# Sheet1.net
KiCad netlist of a schematic drawn in Altium Designer
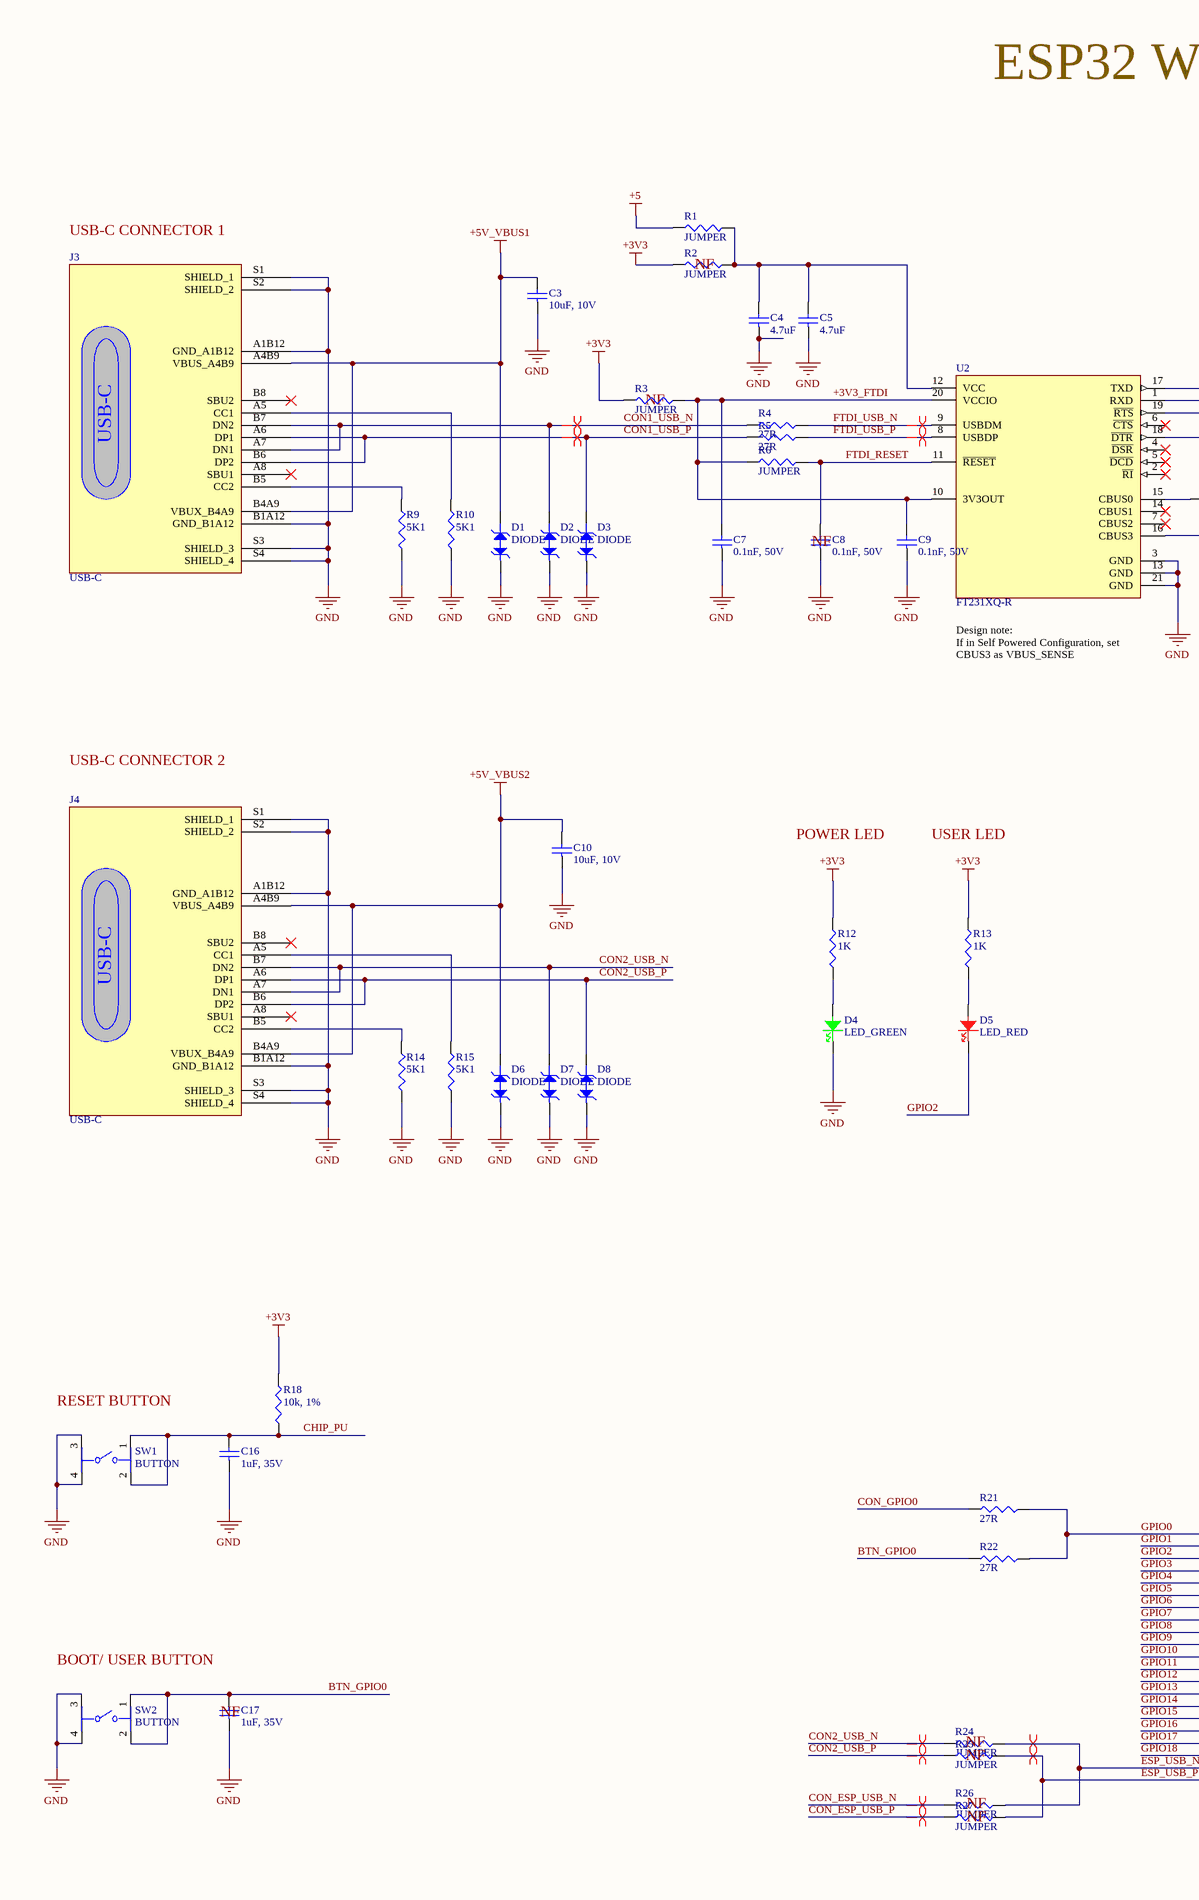
[diagram p0: Sheet1.SchDoc, left]
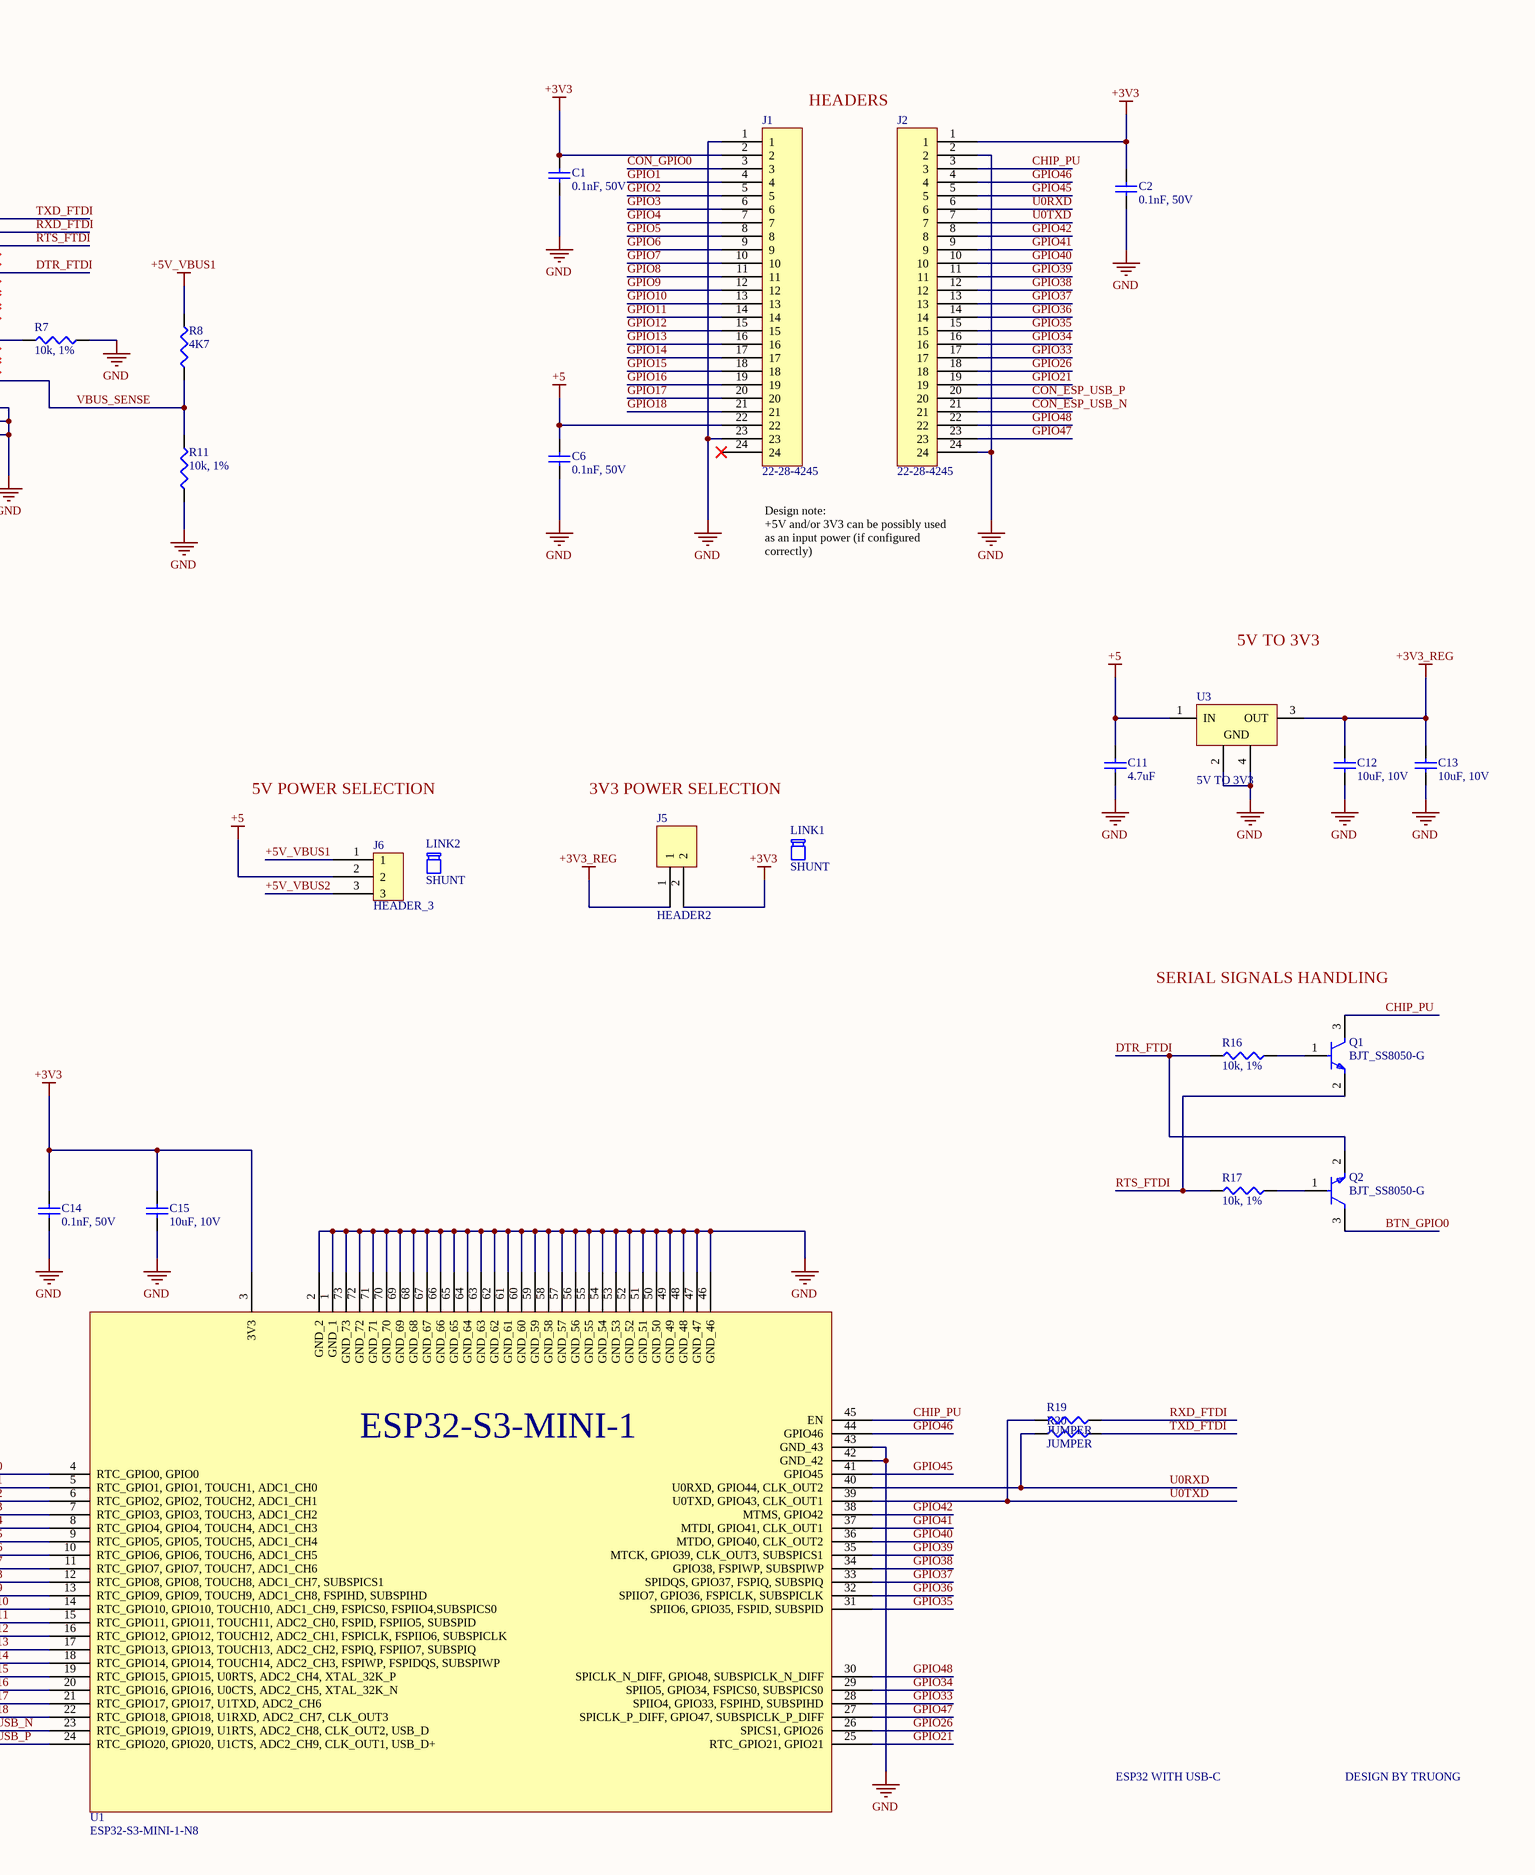
[diagram p1: Sheet1.SchDoc, right]

(export (version "E")
  (design (tool "Eeschema 10.0.6"))
  (components
    (comp (ref "C1")
      (value "0.1nF, 50V")
      (footprint "CAPC1005X70N")
      (description "CAP CER 0.1UF 50V X7R 0402")
      (fields
        (field (name "MANUFACTURER") "Samsung Electro-Mechanics")
        (field (name "MANUFACTURER PART NUMBER") "CL05B104KB5NNWC")
      )
      (libsource (lib "ESP32_CUSTOM_SCH.PrjPcb") (part "CL05B104KB5NNWC"))
    )
    (comp (ref "C2")
      (value "0.1nF, 50V")
      (footprint "CAPC1005X70N")
      (description "CAP CER 0.1UF 50V X7R 0402")
      (fields
        (field (name "MANUFACTURER") "Samsung Electro-Mechanics")
        (field (name "MANUFACTURER PART NUMBER") "CL05B104KB5NNWC")
      )
      (libsource (lib "ESP32_CUSTOM_SCH.PrjPcb") (part "CL05B104KB5NNWC"))
    )
    (comp (ref "C3")
      (value "10uF, 10V")
      (footprint "CAPC1005X70N")
      (description "CAP CER 10UF 10V X5R 0402")
      (fields
        (field (name "MANUFACTURER") "Samsung Electro-Mechanics")
        (field (name "MANUFACTURER PART NUMBER") "CL05A106MP5NUNC")
      )
      (libsource (lib "ESP32_CUSTOM_SCH.PrjPcb") (part "CL05A106MP5NUNC"))
    )
    (comp (ref "C4")
      (value "4.7uF")
      (footprint "CAPC1005X70N")
      (description "CAP CER 4.7UF 16V X5R 0402")
      (fields
        (field (name "MANUFACTURER") "Samsung Electro-Mechanics")
        (field (name "MANUFACTURER PART NUMBER") "CL05A475MO5NUNC")
      )
      (libsource (lib "ESP32_CUSTOM_SCH.PrjPcb") (part "CL05A475MO5NUNC"))
    )
    (comp (ref "C5")
      (value "4.7uF")
      (footprint "CAPC1005X70N")
      (description "CAP CER 4.7UF 16V X5R 0402")
      (fields
        (field (name "MANUFACTURER") "Samsung Electro-Mechanics")
        (field (name "MANUFACTURER PART NUMBER") "CL05A475MO5NUNC")
      )
      (libsource (lib "ESP32_CUSTOM_SCH.PrjPcb") (part "CL05A475MO5NUNC"))
    )
    (comp (ref "C6")
      (value "0.1nF, 50V")
      (footprint "CAPC1005X70N")
      (description "CAP CER 0.1UF 50V X7R 0402")
      (fields
        (field (name "MANUFACTURER") "Samsung Electro-Mechanics")
        (field (name "MANUFACTURER PART NUMBER") "CL05B104KB5NNWC")
      )
      (libsource (lib "ESP32_CUSTOM_SCH.PrjPcb") (part "CL05B104KB5NNWC"))
    )
    (comp (ref "C7")
      (value "0.1nF, 50V")
      (footprint "CAPC1005X70N")
      (description "CAP CER 0.1UF 50V X7R 0402")
      (fields
        (field (name "MANUFACTURER") "Samsung Electro-Mechanics")
        (field (name "MANUFACTURER PART NUMBER") "CL05B104KB5NNWC")
      )
      (libsource (lib "ESP32_CUSTOM_SCH.PrjPcb") (part "CL05B104KB5NNWC"))
    )
    (comp (ref "C8")
      (value "0.1nF, 50V")
      (footprint "CAPC1005X70N")
      (description "CAP CER 0.1UF 50V X7R 0402")
      (fields
        (field (name "MANUFACTURER") "Samsung Electro-Mechanics")
        (field (name "MANUFACTURER PART NUMBER") "CL05B104KB5NNWC")
      )
      (libsource (lib "ESP32_CUSTOM_SCH.PrjPcb") (part "CL05B104KB5NNWC"))
    )
    (comp (ref "C9")
      (value "0.1nF, 50V")
      (footprint "CAPC1005X70N")
      (description "CAP CER 0.1UF 50V X7R 0402")
      (fields
        (field (name "MANUFACTURER") "Samsung Electro-Mechanics")
        (field (name "MANUFACTURER PART NUMBER") "CL05B104KB5NNWC")
      )
      (libsource (lib "ESP32_CUSTOM_SCH.PrjPcb") (part "CL05B104KB5NNWC"))
    )
    (comp (ref "C10")
      (value "10uF, 10V")
      (footprint "CAPC1005X70N")
      (description "CAP CER 10UF 10V X5R 0402")
      (fields
        (field (name "MANUFACTURER") "Samsung Electro-Mechanics")
        (field (name "MANUFACTURER PART NUMBER") "CL05A106MP5NUNC")
      )
      (libsource (lib "ESP32_CUSTOM_SCH.PrjPcb") (part "CL05A106MP5NUNC"))
    )
    (comp (ref "C11")
      (value "4.7uF")
      (footprint "CAPC1005X70N")
      (description "CAP CER 4.7UF 16V X5R 0402")
      (fields
        (field (name "MANUFACTURER") "Samsung Electro-Mechanics")
        (field (name "MANUFACTURER PART NUMBER") "CL05A475MO5NUNC")
      )
      (libsource (lib "ESP32_CUSTOM_SCH.PrjPcb") (part "CL05A475MO5NUNC"))
    )
    (comp (ref "C12")
      (value "10uF, 10V")
      (footprint "CAPC1005X70N")
      (description "CAP CER 10UF 10V X5R 0402")
      (fields
        (field (name "MANUFACTURER") "Samsung Electro-Mechanics")
        (field (name "MANUFACTURER PART NUMBER") "CL05A106MP5NUNC")
      )
      (libsource (lib "ESP32_CUSTOM_SCH.PrjPcb") (part "CL05A106MP5NUNC"))
    )
    (comp (ref "C13")
      (value "10uF, 10V")
      (footprint "CAPC1005X70N")
      (description "CAP CER 10UF 10V X5R 0402")
      (fields
        (field (name "MANUFACTURER") "Samsung Electro-Mechanics")
        (field (name "MANUFACTURER PART NUMBER") "CL05A106MP5NUNC")
      )
      (libsource (lib "ESP32_CUSTOM_SCH.PrjPcb") (part "CL05A106MP5NUNC"))
    )
    (comp (ref "C14")
      (value "0.1nF, 50V")
      (footprint "CAPC1005X70N")
      (description "CAP CER 0.1UF 50V X7R 0402")
      (fields
        (field (name "MANUFACTURER") "Samsung Electro-Mechanics")
        (field (name "MANUFACTURER PART NUMBER") "CL05B104KB5NNWC")
      )
      (libsource (lib "ESP32_CUSTOM_SCH.PrjPcb") (part "CL05B104KB5NNWC"))
    )
    (comp (ref "C15")
      (value "10uF, 10V")
      (footprint "CAPC1005X70N")
      (description "CAP CER 10UF 10V X5R 0402")
      (fields
        (field (name "MANUFACTURER") "Samsung Electro-Mechanics")
        (field (name "MANUFACTURER PART NUMBER") "CL05A106MP5NUNC")
      )
      (libsource (lib "ESP32_CUSTOM_SCH.PrjPcb") (part "CL05A106MP5NUNC"))
    )
    (comp (ref "C16")
      (value "1uF, 35V")
      (footprint "CAPC1005X70N")
      (description "CAP CER 1UF 35V X5R 0402")
      (fields
        (field (name "MANUFACTURER") "Murata")
        (field (name "MANUFACTURER PART NUMBER") "GRM155R6YA105KE11D")
      )
      (libsource (lib "ESP32_CUSTOM_SCH.PrjPcb") (part "GRM155R6YA105KE11D"))
    )
    (comp (ref "C17")
      (value "1uF, 35V")
      (footprint "CAPC1005X70N")
      (description "CAP CER 1UF 35V X5R 0402")
      (fields
        (field (name "MANUFACTURER") "Murata")
        (field (name "MANUFACTURER PART NUMBER") "GRM155R6YA105KE11D")
      )
      (libsource (lib "ESP32_CUSTOM_SCH.PrjPcb") (part "GRM155R6YA105KE11D"))
    )
    (comp (ref "D1")
      (value "DIODE")
      (footprint "SOD882")
      (description "TVS DIODE 5.3VWM 12VC SOD882")
      (fields
        (field (name "MANUFACTURER") "Littelfuse")
        (field (name "MANUFACTURER PART NUMBER") "AQ3045-01ETG")
      )
      (libsource (lib "ESP32_CUSTOM_SCH.PrjPcb") (part "AQ3045-01ETG"))
    )
    (comp (ref "D2")
      (value "DIODE")
      (footprint "SOD882")
      (description "TVS DIODE 5.3VWM 12VC SOD882")
      (fields
        (field (name "MANUFACTURER") "Littelfuse")
        (field (name "MANUFACTURER PART NUMBER") "AQ3045-01ETG")
      )
      (libsource (lib "ESP32_CUSTOM_SCH.PrjPcb") (part "AQ3045-01ETG"))
    )
    (comp (ref "D3")
      (value "DIODE")
      (footprint "SOD882")
      (description "TVS DIODE 5.3VWM 12VC SOD882")
      (fields
        (field (name "MANUFACTURER") "Littelfuse")
        (field (name "MANUFACTURER PART NUMBER") "AQ3045-01ETG")
      )
      (libsource (lib "ESP32_CUSTOM_SCH.PrjPcb") (part "AQ3045-01ETG"))
    )
    (comp (ref "D4")
      (value "LED_GREEN")
      (footprint "LED0402_GREEN")
      (description "LED GREEN 0402 SMD")
      (fields
        (field (name "MANUFACTURER") "Vishay")
        (field (name "MANUFACTURER PART NUMBER") "VLMTG1500-GS08")
      )
      (libsource (lib "ESP32_CUSTOM_SCH.PrjPcb") (part "VLMTG1500-GS08"))
    )
    (comp (ref "D5")
      (value "LED_RED")
      (footprint "LED0402_RED")
      (description "LED RED 0402 SMD")
      (fields
        (field (name "MANUFACTURER") "Vishay")
        (field (name "MANUFACTURER PART NUMBER") "VLMS1500-GS08")
      )
      (libsource (lib "ESP32_CUSTOM_SCH.PrjPcb") (part "VLMS1500-GS08"))
    )
    (comp (ref "D6")
      (value "DIODE")
      (footprint "SOD882")
      (description "TVS DIODE 5.3VWM 12VC SOD882")
      (fields
        (field (name "MANUFACTURER") "Littelfuse")
        (field (name "MANUFACTURER PART NUMBER") "AQ3045-01ETG")
      )
      (libsource (lib "ESP32_CUSTOM_SCH.PrjPcb") (part "AQ3045-01ETG"))
    )
    (comp (ref "D7")
      (value "DIODE")
      (footprint "SOD882")
      (description "TVS DIODE 5.3VWM 12VC SOD882")
      (fields
        (field (name "MANUFACTURER") "Littelfuse")
        (field (name "MANUFACTURER PART NUMBER") "AQ3045-01ETG")
      )
      (libsource (lib "ESP32_CUSTOM_SCH.PrjPcb") (part "AQ3045-01ETG"))
    )
    (comp (ref "D8")
      (value "DIODE")
      (footprint "SOD882")
      (description "TVS DIODE 5.3VWM 12VC SOD882")
      (fields
        (field (name "MANUFACTURER") "Littelfuse")
        (field (name "MANUFACTURER PART NUMBER") "AQ3045-01ETG")
      )
      (libsource (lib "ESP32_CUSTOM_SCH.PrjPcb") (part "AQ3045-01ETG"))
    )
    (comp (ref "J1")
      (value "22-28-4245")
      (footprint "HDR_1X24_2.55MM")
      (description "CONN HEADER VERT 24POS 2.54MM")
      (fields (field (name "MANUFACTURER") "Molex") (field (name "LCSC PART NUMBER") "C7145888"))
      (libsource (lib "") (part "22-28-4245_1"))
    )
    (comp (ref "J2")
      (value "22-28-4245")
      (footprint "HDR_1X24_2.55MM")
      (description "CONN HEADER VERT 24POS 2.54MM")
      (fields (field (name "MANUFACTURER") "Molex") (field (name "LCSC PART NUMBER") "C7145888"))
      (libsource (lib "ESP32_CUSTOM_SCH.PrjPcb") (part "22-28-4245"))
    )
    (comp (ref "J3")
      (value "USB-C")
      (footprint "FP-2171790001-MFG")
      (description "CONN RCP USB2.0 TYP C 24P SMD RA")
      (fields (field (name "MANUFACTURER") "Molex") (field (name "MANUFACTURER PART NUMBER") "217179-0001"))
      (libsource (lib "ESP32_CUSTOM_SCH.PrjPcb") (part "217179-0001"))
    )
    (comp (ref "J4")
      (value "USB-C")
      (footprint "FP-2171790001-MFG")
      (description "CONN RCP USB2.0 TYP C 24P SMD RA")
      (fields (field (name "MANUFACTURER") "Molex") (field (name "MANUFACTURER PART NUMBER") "217179-0001"))
      (libsource (lib "ESP32_CUSTOM_SCH.PrjPcb") (part "217179-0001"))
    )
    (comp (ref "J5")
      (value "HEADER2")
      (footprint "HDR_1X2_1.27MM")
      (description "CONN HEADER VERT 2POS 1.27MM")
      (fields
        (field (name "MANUFACTURER") "Samtec")
        (field (name "MANUFACTURER PART NUMBER") "FTS-102-01-L-S")
      )
      (libsource (lib "ESP32_CUSTOM_SCH.PrjPcb") (part "FTS-102-01-L-S"))
    )
    (comp (ref "J6")
      (value "HEADER_3")
      (footprint "HDR_1X3_1.27MM")
      (description "CONN HEADER VERT 3POS 1.27MM")
      (fields
        (field (name "MANUFACTURER") "Samtec")
        (field (name "MANUFACTURER PART NUMBER") "FTS-103-01-F-S")
      )
      (libsource (lib "ESP32_CUSTOM_SCH.PrjPcb") (part "FTS-103-01-F-S"))
    )
    (comp (ref "LINK1")
      (value "SHUNT")
      (description "CONN SHUNT 1.27MM RED")
      (fields (field (name "MANUFACTURER") "Harwin") (field (name "MANUFACTURER PART NUMBER") "M50-1920005"))
      (libsource (lib "ESP32_CUSTOM_SCH.PrjPcb") (part "M50-1920005"))
    )
    (comp (ref "LINK2")
      (value "SHUNT")
      (description "CONN SHUNT 1.27MM RED")
      (fields (field (name "MANUFACTURER") "Harwin") (field (name "MANUFACTURER PART NUMBER") "M50-1920005"))
      (libsource (lib "ESP32_CUSTOM_SCH.PrjPcb") (part "M50-1920005"))
    )
    (comp (ref "Q1")
      (value "BJT_SS8050-G")
      (footprint "FP-SS8050-G-IPC_B")
      (description "TRANS NPN 25V 1.5A SOT-23-3")
      (fields (field (name "MANUFACTURER") "Comchip") (field (name "MANUFACTURER PART NUMBER") "SS8050-G"))
      (libsource (lib "ESP32_CUSTOM_SCH.PrjPcb") (part "SS8050-G"))
    )
    (comp (ref "Q2")
      (value "BJT_SS8050-G")
      (footprint "FP-SS8050-G-IPC_B")
      (description "TRANS NPN 25V 1.5A SOT-23-3")
      (fields (field (name "MANUFACTURER") "Comchip") (field (name "MANUFACTURER PART NUMBER") "SS8050-G"))
      (libsource (lib "ESP32_CUSTOM_SCH.PrjPcb") (part "SS8050-G"))
    )
    (comp (ref "R1")
      (value "JUMPER")
      (footprint "RESC1005X40N")
      (description "RES 0 OHM JUMPER 1/16W 0402")
      (fields
        (field (name "MANUFACTURER") "Yageo Group")
        (field (name "MANUFACTURER PART NUMBER") "RC0402JR-070RL")
      )
      (libsource (lib "ESP32_CUSTOM_SCH.PrjPcb") (part "RC0402JR-070RL"))
    )
    (comp (ref "R2")
      (value "JUMPER")
      (footprint "RESC1005X40N")
      (description "RES 0 OHM JUMPER 1/16W 0402")
      (fields
        (field (name "MANUFACTURER") "Yageo Group")
        (field (name "MANUFACTURER PART NUMBER") "RC0402JR-070RL")
      )
      (libsource (lib "ESP32_CUSTOM_SCH.PrjPcb") (part "RC0402JR-070RL"))
    )
    (comp (ref "R3")
      (value "JUMPER")
      (footprint "RESC1005X40N")
      (description "RES 0 OHM JUMPER 1/16W 0402")
      (fields
        (field (name "MANUFACTURER") "Yageo Group")
        (field (name "MANUFACTURER PART NUMBER") "RC0402JR-070RL")
      )
      (libsource (lib "ESP32_CUSTOM_SCH.PrjPcb") (part "RC0402JR-070RL"))
    )
    (comp (ref "R4")
      (value "27R")
      (footprint "RESC1005X40N")
      (description "RES 27 OHM 1% 1/16W 0402")
      (fields
        (field (name "MANUFACTURER") "Yageo Group")
        (field (name "MANUFACTURER PART NUMBER") "RC0402FR-0727RL")
      )
      (libsource (lib "ESP32_CUSTOM_SCH.PrjPcb") (part "RC0402FR-0727RL"))
    )
    (comp (ref "R5")
      (value "27R")
      (footprint "RESC1005X40N")
      (description "RES 27 OHM 1% 1/16W 0402")
      (fields
        (field (name "MANUFACTURER") "Yageo Group")
        (field (name "MANUFACTURER PART NUMBER") "RC0402FR-0727RL")
      )
      (libsource (lib "ESP32_CUSTOM_SCH.PrjPcb") (part "RC0402FR-0727RL"))
    )
    (comp (ref "R6")
      (value "JUMPER")
      (footprint "RESC1005X40N")
      (description "RES 0 OHM JUMPER 1/16W 0402")
      (fields
        (field (name "MANUFACTURER") "Yageo Group")
        (field (name "MANUFACTURER PART NUMBER") "RC0402JR-070RL")
      )
      (libsource (lib "ESP32_CUSTOM_SCH.PrjPcb") (part "RC0402JR-070RL"))
    )
    (comp (ref "R7")
      (value "10k, 1%")
      (footprint "RESC1005X40N")
      (description "RES 10K OHM 1% 1/16W 0402")
      (fields
        (field (name "MANUFACTURER") "Yageo Group")
        (field (name "MANUFACTURER PART NUMBER") "RC0402FR-0710KL")
      )
      (libsource (lib "ESP32_CUSTOM_SCH.PrjPcb") (part "RC0402FR-0710KL"))
    )
    (comp (ref "R8")
      (value "4K7")
      (footprint "RESC1005X40N")
      (description "RES 4.7K OHM 1% 1/16W 0402")
      (fields
        (field (name "MANUFACTURER") "Yageo Group")
        (field (name "MANUFACTURER PART NUMBER") "RC0402FR-074K7L")
      )
      (libsource (lib "ESP32_CUSTOM_SCH.PrjPcb") (part "RC0402FR-074K7L"))
    )
    (comp (ref "R9")
      (value "5K1")
      (footprint "RESC1005X40N")
      (description "RES 5.1K OHM 1% 1/16W 0402")
      (fields
        (field (name "MANUFACTURER") "Yageo Group")
        (field (name "MANUFACTURER PART NUMBER") "RC0402FR-07510KL")
      )
      (libsource (lib "ESP32_CUSTOM_SCH.PrjPcb") (part "RC0402FR-07510KL"))
    )
    (comp (ref "R10")
      (value "5K1")
      (footprint "RESC1005X40N")
      (description "RES 5.1K OHM 1% 1/16W 0402")
      (fields
        (field (name "MANUFACTURER") "Yageo Group")
        (field (name "MANUFACTURER PART NUMBER") "RC0402FR-07510KL")
      )
      (libsource (lib "ESP32_CUSTOM_SCH.PrjPcb") (part "RC0402FR-07510KL"))
    )
    (comp (ref "R11")
      (value "10k, 1%")
      (footprint "RESC1005X40N")
      (description "RES 10K OHM 1% 1/16W 0402")
      (fields
        (field (name "MANUFACTURER") "Yageo Group")
        (field (name "MANUFACTURER PART NUMBER") "RC0402FR-0710KL")
      )
      (libsource (lib "ESP32_CUSTOM_SCH.PrjPcb") (part "RC0402FR-0710KL"))
    )
    (comp (ref "R12")
      (value "1K")
      (footprint "RESC1005X40N")
      (description "RES 1K OHM 5% 1/16W 0402")
      (fields
        (field (name "MANUFACTURER") "Yageo Group")
        (field (name "MANUFACTURER PART NUMBER") "RC0402JR-071KL")
      )
      (libsource (lib "ESP32_CUSTOM_SCH.PrjPcb") (part "RC0402JR-071KL"))
    )
    (comp (ref "R13")
      (value "1K")
      (footprint "RESC1005X40N")
      (description "RES 1K OHM 5% 1/16W 0402")
      (fields
        (field (name "MANUFACTURER") "Yageo Group")
        (field (name "MANUFACTURER PART NUMBER") "RC0402JR-071KL")
      )
      (libsource (lib "ESP32_CUSTOM_SCH.PrjPcb") (part "RC0402JR-071KL"))
    )
    (comp (ref "R14")
      (value "5K1")
      (footprint "RESC1005X40N")
      (description "RES 5.1K OHM 1% 1/16W 0402")
      (fields
        (field (name "MANUFACTURER") "Yageo Group")
        (field (name "MANUFACTURER PART NUMBER") "RC0402FR-07510KL")
      )
      (libsource (lib "ESP32_CUSTOM_SCH.PrjPcb") (part "RC0402FR-07510KL"))
    )
    (comp (ref "R15")
      (value "5K1")
      (footprint "RESC1005X40N")
      (description "RES 5.1K OHM 1% 1/16W 0402")
      (fields
        (field (name "MANUFACTURER") "Yageo Group")
        (field (name "MANUFACTURER PART NUMBER") "RC0402FR-07510KL")
      )
      (libsource (lib "ESP32_CUSTOM_SCH.PrjPcb") (part "RC0402FR-07510KL"))
    )
    (comp (ref "R16")
      (value "10k, 1%")
      (footprint "RESC1005X40N")
      (description "RES 10K OHM 1% 1/16W 0402")
      (fields
        (field (name "MANUFACTURER") "Yageo Group")
        (field (name "MANUFACTURER PART NUMBER") "RC0402FR-0710KL")
      )
      (libsource (lib "ESP32_CUSTOM_SCH.PrjPcb") (part "RC0402FR-0710KL"))
    )
    (comp (ref "R17")
      (value "10k, 1%")
      (footprint "RESC1005X40N")
      (description "RES 10K OHM 1% 1/16W 0402")
      (fields
        (field (name "MANUFACTURER") "Yageo Group")
        (field (name "MANUFACTURER PART NUMBER") "RC0402FR-0710KL")
      )
      (libsource (lib "ESP32_CUSTOM_SCH.PrjPcb") (part "RC0402FR-0710KL"))
    )
    (comp (ref "R18")
      (value "10k, 1%")
      (footprint "RESC1005X40N")
      (description "RES 10K OHM 1% 1/16W 0402")
      (fields
        (field (name "MANUFACTURER") "Yageo Group")
        (field (name "MANUFACTURER PART NUMBER") "RC0402FR-0710KL")
      )
      (libsource (lib "ESP32_CUSTOM_SCH.PrjPcb") (part "RC0402FR-0710KL"))
    )
    (comp (ref "R19")
      (value "JUMPER")
      (footprint "RESC1005X40N")
      (description "RES 0 OHM JUMPER 1/16W 0402")
      (fields
        (field (name "MANUFACTURER") "Yageo Group")
        (field (name "MANUFACTURER PART NUMBER") "RC0402JR-070RL")
      )
      (libsource (lib "ESP32_CUSTOM_SCH.PrjPcb") (part "RC0402JR-070RL"))
    )
    (comp (ref "R20")
      (value "JUMPER")
      (footprint "RESC1005X40N")
      (description "RES 0 OHM JUMPER 1/16W 0402")
      (fields
        (field (name "MANUFACTURER") "Yageo Group")
        (field (name "MANUFACTURER PART NUMBER") "RC0402JR-070RL")
      )
      (libsource (lib "ESP32_CUSTOM_SCH.PrjPcb") (part "RC0402JR-070RL"))
    )
    (comp (ref "R21")
      (value "27R")
      (footprint "RESC1005X40N")
      (description "RES 27 OHM 1% 1/16W 0402")
      (fields
        (field (name "MANUFACTURER") "Yageo Group")
        (field (name "MANUFACTURER PART NUMBER") "RC0402FR-0727RL")
      )
      (libsource (lib "ESP32_CUSTOM_SCH.PrjPcb") (part "RC0402FR-0727RL"))
    )
    (comp (ref "R22")
      (value "27R")
      (footprint "RESC1005X40N")
      (description "RES 27 OHM 1% 1/16W 0402")
      (fields
        (field (name "MANUFACTURER") "Yageo Group")
        (field (name "MANUFACTURER PART NUMBER") "RC0402FR-0727RL")
      )
      (libsource (lib "ESP32_CUSTOM_SCH.PrjPcb") (part "RC0402FR-0727RL"))
    )
    (comp (ref "R24")
      (value "JUMPER")
      (footprint "RESC1005X40N")
      (description "RES 0 OHM JUMPER 1/16W 0402")
      (fields
        (field (name "MANUFACTURER") "Yageo Group")
        (field (name "MANUFACTURER PART NUMBER") "RC0402JR-070RL")
      )
      (libsource (lib "ESP32_CUSTOM_SCH.PrjPcb") (part "RC0402JR-070RL"))
    )
    (comp (ref "R25")
      (value "JUMPER")
      (footprint "RESC1005X40N")
      (description "RES 0 OHM JUMPER 1/16W 0402")
      (fields
        (field (name "MANUFACTURER") "Yageo Group")
        (field (name "MANUFACTURER PART NUMBER") "RC0402JR-070RL")
      )
      (libsource (lib "ESP32_CUSTOM_SCH.PrjPcb") (part "RC0402JR-070RL"))
    )
    (comp (ref "R26")
      (value "JUMPER")
      (footprint "RESC1005X40N")
      (description "RES 0 OHM JUMPER 1/16W 0402")
      (fields
        (field (name "MANUFACTURER") "Yageo Group")
        (field (name "MANUFACTURER PART NUMBER") "RC0402JR-070RL")
      )
      (libsource (lib "ESP32_CUSTOM_SCH.PrjPcb") (part "RC0402JR-070RL"))
    )
    (comp (ref "R27")
      (value "JUMPER")
      (footprint "RESC1005X40N")
      (description "RES 0 OHM JUMPER 1/16W 0402")
      (fields
        (field (name "MANUFACTURER") "Yageo Group")
        (field (name "MANUFACTURER PART NUMBER") "RC0402JR-070RL")
      )
      (libsource (lib "ESP32_CUSTOM_SCH.PrjPcb") (part "RC0402JR-070RL"))
    )
    (comp (ref "SW1")
      (value "BUTTON")
      (footprint "FP-PTS645SM43SMTR92LFS-MFG")
      (description "SWITCH TACTILE SPST-NO 0.05A 12V")
      (fields
        (field (name "MANUFACTURER") "C&K Components")
        (field (name "MANUFACTURER PART NUMBER") "PTS645SM43SMTR92LFS")
      )
      (libsource (lib "ESP32_CUSTOM_SCH.PrjPcb") (part "PTS645SM43SMTR92LFS"))
    )
    (comp (ref "SW2")
      (value "BUTTON")
      (footprint "FP-PTS645SM43SMTR92LFS-MFG")
      (description "SWITCH TACTILE SPST-NO 0.05A 12V")
      (fields
        (field (name "MANUFACTURER") "C&K Components")
        (field (name "MANUFACTURER PART NUMBER") "PTS645SM43SMTR92LFS")
      )
      (libsource (lib "ESP32_CUSTOM_SCH.PrjPcb") (part "PTS645SM43SMTR92LFS"))
    )
    (comp (ref "U1")
      (value "ESP32-S3-MINI-1-N8")
      (footprint "XCVR_ESP32-S3-MINI-1-N8")
      (description "20.5dBm ESP32-S3FN8 Chip 2.4GHz SMD WiFi Modules ROHS")
      (fields (field (name "MANUFACTURER") "Espressif Systems") (field (name "LCSC PART NUMBER") "C2913206"))
      (libsource (lib "ESP32_CUSTOM_SCH.PrjPcb") (part "ESP32-S3-MINI-1-N8 (2)"))
    )
    (comp (ref "U2")
      (value "FT231XQ-R")
      (footprint "FP-QFN-20-IPC_B")
      (description "IC USB SERIAL FULL UART 20QFN")
      (fields (field (name "MANUFACTURER") "FTDI") (field (name "LCSC PART NUMBER") "C132159"))
      (libsource (lib "ESP32_CUSTOM_SCH.PrjPcb") (part "FT231XQ-R"))
    )
    (comp (ref "U3")
      (value "5V TO 3V3")
      (footprint "DCY0004A_N")
      (description "IC REG LIN 3.3V 1.5A SOT-223-4")
      (fields
        (field (name "MANUFACTURER") "Texas Instruments")
        (field (name "MANUFACTURER PART NUMBER") "TL1963A-33DCYR")
      )
      (libsource (lib "ESP32_CUSTOM_SCH.PrjPcb") (part "TL1963A-33DCYR"))
    )
  )
  (nets
    (net (code "1") (name "+3V3") (class "Default")
      (node (ref "C1") (pin "2") (pinfunction "2_2") (pintype "passive"))
      (node (ref "C14") (pin "2") (pinfunction "2_2") (pintype "passive"))
      (node (ref "C15") (pin "2") (pinfunction "2_2") (pintype "passive"))
      (node (ref "C2") (pin "2") (pinfunction "2_2") (pintype "passive"))
      (node (ref "J1") (pin "2") (pinfunction "2_2") (pintype "passive"))
      (node (ref "J2") (pin "1") (pinfunction "1_1") (pintype "passive"))
      (node (ref "J5") (pin "2") (pinfunction "2_2") (pintype "passive"))
      (node (ref "R12") (pin "2") (pinfunction "2_2") (pintype "passive"))
      (node (ref "R13") (pin "2") (pinfunction "2_2") (pintype "passive"))
      (node (ref "R18") (pin "2") (pinfunction "2_2") (pintype "passive"))
      (node (ref "R2") (pin "1") (pinfunction "1_1") (pintype "passive"))
      (node (ref "R3") (pin "1") (pinfunction "1_1") (pintype "passive"))
      (node (ref "U1") (pin "3") (pinfunction "3V3_3") (pintype "passive"))
    )
    (net (code "2") (name "+3V3_REG") (class "Default")
      (node (ref "C12") (pin "2") (pinfunction "2_2") (pintype "passive"))
      (node (ref "C13") (pin "2") (pinfunction "2_2") (pintype "passive"))
      (node (ref "J5") (pin "1") (pinfunction "1_1") (pintype "passive"))
      (node (ref "U3") (pin "3") (pinfunction "OUT_3") (pintype "power_in"))
    )
    (net (code "3") (name "+5") (class "Default")
      (node (ref "C11") (pin "2") (pinfunction "2_2") (pintype "passive"))
      (node (ref "C6") (pin "2") (pinfunction "2_2") (pintype "passive"))
      (node (ref "J1") (pin "22") (pinfunction "22_22") (pintype "passive"))
      (node (ref "J6") (pin "2") (pinfunction "2_2") (pintype "passive"))
      (node (ref "R1") (pin "1") (pinfunction "1_1") (pintype "passive"))
      (node (ref "U3") (pin "1") (pinfunction "IN_1") (pintype "power_in"))
    )
    (net (code "4") (name "+5V_VBUS1") (class "Default")
      (node (ref "C3") (pin "2") (pinfunction "2_2") (pintype "passive"))
      (node (ref "D1") (pin "2") (pinfunction "2_2") (pintype "passive"))
      (node (ref "J3") (pin "A4B9") (pinfunction "VBUS_A4B9_A4B9") (pintype "passive"))
      (node (ref "J3") (pin "B4A9") (pinfunction "VBUX_B4A9_B4A9") (pintype "passive"))
      (node (ref "J6") (pin "1") (pinfunction "1_1") (pintype "passive"))
      (node (ref "R8") (pin "2") (pinfunction "2_2") (pintype "passive"))
    )
    (net (code "5") (name "+5V_VBUS2") (class "Default")
      (node (ref "C10") (pin "2") (pinfunction "2_2") (pintype "passive"))
      (node (ref "D6") (pin "2") (pinfunction "2_2") (pintype "passive"))
      (node (ref "J4") (pin "A4B9") (pinfunction "VBUS_A4B9_A4B9") (pintype "passive"))
      (node (ref "J4") (pin "B4A9") (pinfunction "VBUX_B4A9_B4A9") (pintype "passive"))
      (node (ref "J6") (pin "3") (pinfunction "3_3") (pintype "passive"))
    )
    (net (code "6") (name "/+3V3_FTDI") (class "Default")
      (node (ref "C7") (pin "2") (pinfunction "2_2") (pintype "passive"))
      (node (ref "C9") (pin "2") (pinfunction "2_2") (pintype "passive"))
      (node (ref "R3") (pin "2") (pinfunction "2_2") (pintype "passive"))
      (node (ref "R6") (pin "1") (pinfunction "1_1") (pintype "passive"))
      (node (ref "U2") (pin "10") (pinfunction "3V3OUT_10") (pintype "passive"))
      (node (ref "U2") (pin "20") (pinfunction "VCCIO_20") (pintype "passive"))
    )
    (net (code "7") (name "/BTN_GPIO0") (class "Default")
      (node (ref "C17") (pin "2") (pinfunction "2_2") (pintype "passive"))
      (node (ref "Q2") (pin "3") (pinfunction "C_3") (pintype "passive"))
      (node (ref "R22") (pin "1") (pinfunction "1_1") (pintype "passive"))
      (node (ref "SW2") (pin "1") (pinfunction "1_1") (pintype "passive"))
      (node (ref "SW2") (pin "2") (pinfunction "2_2") (pintype "passive"))
    )
    (net (code "8") (name "/CHIP_PU") (class "Default")
      (node (ref "C16") (pin "2") (pinfunction "2_2") (pintype "passive"))
      (node (ref "J2") (pin "3") (pinfunction "3_3") (pintype "passive"))
      (node (ref "Q1") (pin "3") (pinfunction "C_3") (pintype "passive"))
      (node (ref "R18") (pin "1") (pinfunction "1_1") (pintype "passive"))
      (node (ref "SW1") (pin "1") (pinfunction "1_1") (pintype "passive"))
      (node (ref "SW1") (pin "2") (pinfunction "2_2") (pintype "passive"))
      (node (ref "U1") (pin "45") (pinfunction "EN_45") (pintype "passive"))
    )
    (net (code "9") (name "/CON1_USB_N") (class "Default")
      (node (ref "D2") (pin "2") (pinfunction "2_2") (pintype "passive"))
      (node (ref "J3") (pin "A7") (pinfunction "DN1_A7") (pintype "passive"))
      (node (ref "J3") (pin "B7") (pinfunction "DN2_B7") (pintype "passive"))
      (node (ref "R4") (pin "1") (pinfunction "1_1") (pintype "passive"))
    )
    (net (code "10") (name "/CON1_USB_P") (class "Default")
      (node (ref "D3") (pin "2") (pinfunction "2_2") (pintype "passive"))
      (node (ref "J3") (pin "A6") (pinfunction "DP1_A6") (pintype "passive"))
      (node (ref "J3") (pin "B6") (pinfunction "DP2_B6") (pintype "passive"))
      (node (ref "R5") (pin "1") (pinfunction "1_1") (pintype "passive"))
    )
    (net (code "11") (name "/CON2_USB_N") (class "Default")
      (node (ref "D7") (pin "2") (pinfunction "2_2") (pintype "passive"))
      (node (ref "J4") (pin "A7") (pinfunction "DN1_A7") (pintype "passive"))
      (node (ref "J4") (pin "B7") (pinfunction "DN2_B7") (pintype "passive"))
      (node (ref "R24") (pin "1") (pinfunction "1_1") (pintype "passive"))
    )
    (net (code "12") (name "/CON2_USB_P") (class "Default")
      (node (ref "D8") (pin "2") (pinfunction "2_2") (pintype "passive"))
      (node (ref "J4") (pin "A6") (pinfunction "DP1_A6") (pintype "passive"))
      (node (ref "J4") (pin "B6") (pinfunction "DP2_B6") (pintype "passive"))
      (node (ref "R25") (pin "1") (pinfunction "1_1") (pintype "passive"))
    )
    (net (code "13") (name "/CON_ESP_USB_N") (class "Default")
      (node (ref "J2") (pin "21") (pinfunction "21_21") (pintype "passive"))
      (node (ref "R26") (pin "1") (pinfunction "1_1") (pintype "passive"))
    )
    (net (code "14") (name "/CON_ESP_USB_P") (class "Default")
      (node (ref "J2") (pin "20") (pinfunction "20_20") (pintype "passive"))
      (node (ref "R27") (pin "1") (pinfunction "1_1") (pintype "passive"))
    )
    (net (code "15") (name "/CON_GPIO0") (class "Default")
      (node (ref "J1") (pin "3") (pinfunction "3_3") (pintype "passive"))
      (node (ref "R21") (pin "1") (pinfunction "1_1") (pintype "passive"))
    )
    (net (code "16") (name "/DTR_FTDI") (class "Default")
      (node (ref "Q2") (pin "2") (pinfunction "E_2") (pintype "passive"))
      (node (ref "R16") (pin "1") (pinfunction "1_1") (pintype "passive"))
      (node (ref "U2") (pin "18") (pinfunction "~{DTR}_18") (pintype "output"))
    )
    (net (code "17") (name "/ESP_USB_N") (class "Default")
      (node (ref "R24") (pin "2") (pinfunction "2_2") (pintype "passive"))
      (node (ref "R26") (pin "2") (pinfunction "2_2") (pintype "passive"))
      (node (ref "U1") (pin "23") (pinfunction "RTC_GPIO19,_GPIO19,_U1RTS,_ADC2_CH8,_CLK_OUT2,_USB_D_23") (pintype "passive"))
    )
    (net (code "18") (name "/ESP_USB_P") (class "Default")
      (node (ref "R25") (pin "2") (pinfunction "2_2") (pintype "passive"))
      (node (ref "R27") (pin "2") (pinfunction "2_2") (pintype "passive"))
      (node (ref "U1") (pin "24") (pinfunction "RTC_GPIO20,_GPIO20,_U1CTS,_ADC2_CH9,_CLK_OUT1,_USB_D+_24") (pintype "passive"))
    )
    (net (code "19") (name "/FTDI_RESET") (class "Default")
      (node (ref "C8") (pin "2") (pinfunction "2_2") (pintype "passive"))
      (node (ref "R6") (pin "2") (pinfunction "2_2") (pintype "passive"))
      (node (ref "U2") (pin "11") (pinfunction "~{RESET}_11") (pintype "passive"))
    )
    (net (code "20") (name "/FTDI_USB_N") (class "Default")
      (node (ref "R4") (pin "2") (pinfunction "2_2") (pintype "passive"))
      (node (ref "U2") (pin "9") (pinfunction "USBDM_9") (pintype "passive"))
    )
    (net (code "21") (name "/FTDI_USB_P") (class "Default")
      (node (ref "R5") (pin "2") (pinfunction "2_2") (pintype "passive"))
      (node (ref "U2") (pin "8") (pinfunction "USBDP_8") (pintype "passive"))
    )
    (net (code "22") (name "/GPIO0") (class "Default")
      (node (ref "R21") (pin "2") (pinfunction "2_2") (pintype "passive"))
      (node (ref "R22") (pin "2") (pinfunction "2_2") (pintype "passive"))
      (node (ref "U1") (pin "4") (pinfunction "RTC_GPIO0,_GPIO0_4") (pintype "passive"))
    )
    (net (code "23") (name "/GPIO1") (class "Default")
      (node (ref "J1") (pin "4") (pinfunction "4_4") (pintype "passive"))
      (node (ref "U1") (pin "5") (pinfunction "RTC_GPIO1,_GPIO1,_TOUCH1,_ADC1_CH0_5") (pintype "passive"))
    )
    (net (code "24") (name "/GPIO2") (class "Default")
      (node (ref "D5") (pin "1") (pinfunction "1_1") (pintype "passive"))
      (node (ref "J1") (pin "5") (pinfunction "5_5") (pintype "passive"))
      (node (ref "U1") (pin "6") (pinfunction "RTC_GPIO2,_GPIO2,_TOUCH2,_ADC1_CH1_6") (pintype "passive"))
    )
    (net (code "25") (name "/GPIO3") (class "Default")
      (node (ref "J1") (pin "6") (pinfunction "6_6") (pintype "passive"))
      (node (ref "U1") (pin "7") (pinfunction "RTC_GPIO3,_GPIO3,_TOUCH3,_ADC1_CH2_7") (pintype "passive"))
    )
    (net (code "26") (name "/GPIO4") (class "Default")
      (node (ref "J1") (pin "7") (pinfunction "7_7") (pintype "passive"))
      (node (ref "U1") (pin "8") (pinfunction "RTC_GPIO4,_GPIO4,_TOUCH4,_ADC1_CH3_8") (pintype "passive"))
    )
    (net (code "27") (name "/GPIO5") (class "Default")
      (node (ref "J1") (pin "8") (pinfunction "8_8") (pintype "passive"))
      (node (ref "U1") (pin "9") (pinfunction "RTC_GPIO5,_GPIO5,_TOUCH5,_ADC1_CH4_9") (pintype "passive"))
    )
    (net (code "28") (name "/GPIO6") (class "Default")
      (node (ref "J1") (pin "9") (pinfunction "9_9") (pintype "passive"))
      (node (ref "U1") (pin "10") (pinfunction "RTC_GPIO6,_GPIO6,_TOUCH6,_ADC1_CH5_10") (pintype "passive"))
    )
    (net (code "29") (name "/GPIO7") (class "Default")
      (node (ref "J1") (pin "10") (pinfunction "10_10") (pintype "passive"))
      (node (ref "U1") (pin "11") (pinfunction "RTC_GPIO7,_GPIO7,_TOUCH7,_ADC1_CH6_11") (pintype "passive"))
    )
    (net (code "30") (name "/GPIO8") (class "Default")
      (node (ref "J1") (pin "11") (pinfunction "11_11") (pintype "passive"))
      (node (ref "U1") (pin "12") (pinfunction "RTC_GPIO8,_GPIO8,_TOUCH8,_ADC1_CH7,_SUBSPICS1_12") (pintype "passive"))
    )
    (net (code "31") (name "/GPIO9") (class "Default")
      (node (ref "J1") (pin "12") (pinfunction "12_12") (pintype "passive"))
      (node (ref "U1") (pin "13") (pinfunction "RTC_GPIO9,_GPIO9,_TOUCH9,_ADC1_CH8,_FSPIHD,_SUBSPIHD_13") (pintype "passive"))
    )
    (net (code "32") (name "/GPIO10") (class "Default")
      (node (ref "J1") (pin "13") (pinfunction "13_13") (pintype "passive"))
      (node (ref "U1") (pin "14") (pinfunction "RTC_GPIO10,_GPIO10,_TOUCH10,_ADC1_CH9,_FSPICS0,_FSPIIO4,SUBSPICS0_14") (pintype "passive"))
    )
    (net (code "33") (name "/GPIO11") (class "Default")
      (node (ref "J1") (pin "14") (pinfunction "14_14") (pintype "passive"))
      (node (ref "U1") (pin "15") (pinfunction "RTC_GPIO11,_GPIO11,_TOUCH11,_ADC2_CH0,_FSPID,_FSPIIO5,_SUBSPID_15") (pintype "passive"))
    )
    (net (code "34") (name "/GPIO12") (class "Default")
      (node (ref "J1") (pin "15") (pinfunction "15_15") (pintype "passive"))
      (node (ref "U1") (pin "16") (pinfunction "RTC_GPIO12,_GPIO12,_TOUCH12,_ADC2_CH1,_FSPICLK,_FSPIIO6,_SUBSPICLK_16") (pintype "passive"))
    )
    (net (code "35") (name "/GPIO13") (class "Default")
      (node (ref "J1") (pin "16") (pinfunction "16_16") (pintype "passive"))
      (node (ref "U1") (pin "17") (pinfunction "RTC_GPIO13,_GPIO13,_TOUCH13,_ADC2_CH2,_FSPIQ,_FSPIIO7,_SUBSPIQ_17") (pintype "passive"))
    )
    (net (code "36") (name "/GPIO14") (class "Default")
      (node (ref "J1") (pin "17") (pinfunction "17_17") (pintype "passive"))
      (node (ref "U1") (pin "18") (pinfunction "RTC_GPIO14,_GPIO14,_TOUCH14,_ADC2_CH3,_FSPIWP,_FSPIDQS,_SUBSPIWP_18") (pintype "passive"))
    )
    (net (code "37") (name "/GPIO15") (class "Default")
      (node (ref "J1") (pin "18") (pinfunction "18_18") (pintype "passive"))
      (node (ref "U1") (pin "19") (pinfunction "RTC_GPIO15,_GPIO15,_U0RTS,_ADC2_CH4,_XTAL_32K_P_19") (pintype "passive"))
    )
    (net (code "38") (name "/GPIO16") (class "Default")
      (node (ref "J1") (pin "19") (pinfunction "19_19") (pintype "passive"))
      (node (ref "U1") (pin "20") (pinfunction "RTC_GPIO16,_GPIO16,_U0CTS,_ADC2_CH5,_XTAL_32K_N_20") (pintype "passive"))
    )
    (net (code "39") (name "/GPIO17") (class "Default")
      (node (ref "J1") (pin "20") (pinfunction "20_20") (pintype "passive"))
      (node (ref "U1") (pin "21") (pinfunction "RTC_GPIO17,_GPIO17,_U1TXD,_ADC2_CH6_21") (pintype "passive"))
    )
    (net (code "40") (name "/GPIO18") (class "Default")
      (node (ref "J1") (pin "21") (pinfunction "21_21") (pintype "passive"))
      (node (ref "U1") (pin "22") (pinfunction "RTC_GPIO18,_GPIO18,_U1RXD,_ADC2_CH7,_CLK_OUT3_22") (pintype "passive"))
    )
    (net (code "41") (name "/GPIO21") (class "Default")
      (node (ref "J2") (pin "19") (pinfunction "19_19") (pintype "passive"))
      (node (ref "U1") (pin "25") (pinfunction "RTC_GPIO21,_GPIO21_25") (pintype "passive"))
    )
    (net (code "42") (name "/GPIO26") (class "Default")
      (node (ref "J2") (pin "18") (pinfunction "18_18") (pintype "passive"))
      (node (ref "U1") (pin "26") (pinfunction "SPICS1,_GPIO26_26") (pintype "passive"))
    )
    (net (code "43") (name "/GPIO33") (class "Default")
      (node (ref "J2") (pin "17") (pinfunction "17_17") (pintype "passive"))
      (node (ref "U1") (pin "28") (pinfunction "SPIIO4,_GPIO33,_FSPIHD,_SUBSPIHD_28") (pintype "passive"))
    )
    (net (code "44") (name "/GPIO34") (class "Default")
      (node (ref "J2") (pin "16") (pinfunction "16_16") (pintype "passive"))
      (node (ref "U1") (pin "29") (pinfunction "SPIIO5,_GPIO34,_FSPICS0,_SUBSPICS0_29") (pintype "passive"))
    )
    (net (code "45") (name "/GPIO35") (class "Default")
      (node (ref "J2") (pin "15") (pinfunction "15_15") (pintype "passive"))
      (node (ref "U1") (pin "31") (pinfunction "SPIIO6,_GPIO35,_FSPID,_SUBSPID_31") (pintype "passive"))
    )
    (net (code "46") (name "/GPIO36") (class "Default")
      (node (ref "J2") (pin "14") (pinfunction "14_14") (pintype "passive"))
      (node (ref "U1") (pin "32") (pinfunction "SPIIO7,_GPIO36,_FSPICLK,_SUBSPICLK_32") (pintype "passive"))
    )
    (net (code "47") (name "/GPIO37") (class "Default")
      (node (ref "J2") (pin "13") (pinfunction "13_13") (pintype "passive"))
      (node (ref "U1") (pin "33") (pinfunction "SPIDQS,_GPIO37,_FSPIQ,_SUBSPIQ_33") (pintype "passive"))
    )
    (net (code "48") (name "/GPIO38") (class "Default")
      (node (ref "J2") (pin "12") (pinfunction "12_12") (pintype "passive"))
      (node (ref "U1") (pin "34") (pinfunction "GPIO38,_FSPIWP,_SUBSPIWP_34") (pintype "passive"))
    )
    (net (code "49") (name "/GPIO39") (class "Default")
      (node (ref "J2") (pin "11") (pinfunction "11_11") (pintype "passive"))
      (node (ref "U1") (pin "35") (pinfunction "MTCK,_GPIO39,_CLK_OUT3,_SUBSPICS1_35") (pintype "passive"))
    )
    (net (code "50") (name "/GPIO40") (class "Default")
      (node (ref "J2") (pin "10") (pinfunction "10_10") (pintype "passive"))
      (node (ref "U1") (pin "36") (pinfunction "MTDO,_GPIO40,_CLK_OUT2_36") (pintype "passive"))
    )
    (net (code "51") (name "/GPIO41") (class "Default")
      (node (ref "J2") (pin "9") (pinfunction "9_9") (pintype "passive"))
      (node (ref "U1") (pin "37") (pinfunction "MTDI,_GPIO41,_CLK_OUT1_37") (pintype "passive"))
    )
    (net (code "52") (name "/GPIO42") (class "Default")
      (node (ref "J2") (pin "8") (pinfunction "8_8") (pintype "passive"))
      (node (ref "U1") (pin "38") (pinfunction "MTMS,_GPIO42_38") (pintype "passive"))
    )
    (net (code "53") (name "/GPIO45") (class "Default")
      (node (ref "J2") (pin "5") (pinfunction "5_5") (pintype "passive"))
      (node (ref "U1") (pin "41") (pinfunction "GPIO45_41") (pintype "passive"))
    )
    (net (code "54") (name "/GPIO46") (class "Default")
      (node (ref "J2") (pin "4") (pinfunction "4_4") (pintype "passive"))
      (node (ref "U1") (pin "44") (pinfunction "GPIO46_44") (pintype "passive"))
    )
    (net (code "55") (name "/GPIO47") (class "Default")
      (node (ref "J2") (pin "23") (pinfunction "23_23") (pintype "passive"))
      (node (ref "U1") (pin "27") (pinfunction "SPICLK_P_DIFF,_GPIO47,_SUBSPICLK_P_DIFF_27") (pintype "passive"))
    )
    (net (code "56") (name "/GPIO48") (class "Default")
      (node (ref "J2") (pin "22") (pinfunction "22_22") (pintype "passive"))
      (node (ref "U1") (pin "30") (pinfunction "SPICLK_N_DIFF,_GPIO48,_SUBSPICLK_N_DIFF_30") (pintype "passive"))
    )
    (net (code "57") (name "/RTS_FTDI") (class "Default")
      (node (ref "Q1") (pin "2") (pinfunction "E_2") (pintype "passive"))
      (node (ref "R17") (pin "1") (pinfunction "1_1") (pintype "passive"))
      (node (ref "U2") (pin "19") (pinfunction "~{RTS}_19") (pintype "output"))
    )
    (net (code "58") (name "/RXD_FTDI") (class "Default")
      (node (ref "R19") (pin "2") (pinfunction "2_2") (pintype "passive"))
      (node (ref "U2") (pin "1") (pinfunction "RXD_1") (pintype "passive"))
    )
    (net (code "59") (name "/TXD_FTDI") (class "Default")
      (node (ref "R20") (pin "2") (pinfunction "2_2") (pintype "passive"))
      (node (ref "U2") (pin "17") (pinfunction "TXD_17") (pintype "output"))
    )
    (net (code "60") (name "/U0RXD") (class "Default")
      (node (ref "J2") (pin "6") (pinfunction "6_6") (pintype "passive"))
      (node (ref "R20") (pin "1") (pinfunction "1_1") (pintype "passive"))
      (node (ref "U1") (pin "40") (pinfunction "U0RXD,_GPIO44,_CLK_OUT2_40") (pintype "passive"))
    )
    (net (code "61") (name "/U0TXD") (class "Default")
      (node (ref "J2") (pin "7") (pinfunction "7_7") (pintype "passive"))
      (node (ref "R19") (pin "1") (pinfunction "1_1") (pintype "passive"))
      (node (ref "U1") (pin "39") (pinfunction "U0TXD,_GPIO43,_CLK_OUT1_39") (pintype "passive"))
    )
    (net (code "62") (name "/VBUS_SENSE") (class "Default")
      (node (ref "R11") (pin "2") (pinfunction "2_2") (pintype "passive"))
      (node (ref "R8") (pin "1") (pinfunction "1_1") (pintype "passive"))
      (node (ref "U2") (pin "16") (pinfunction "CBUS3_16") (pintype "passive"))
    )
    (net (code "63") (name "GND") (class "Default")
      (node (ref "C1") (pin "1") (pinfunction "1_1") (pintype "passive"))
      (node (ref "C10") (pin "1") (pinfunction "1_1") (pintype "passive"))
      (node (ref "C11") (pin "1") (pinfunction "1_1") (pintype "passive"))
      (node (ref "C12") (pin "1") (pinfunction "1_1") (pintype "passive"))
      (node (ref "C13") (pin "1") (pinfunction "1_1") (pintype "passive"))
      (node (ref "C14") (pin "1") (pinfunction "1_1") (pintype "passive"))
      (node (ref "C15") (pin "1") (pinfunction "1_1") (pintype "passive"))
      (node (ref "C16") (pin "1") (pinfunction "1_1") (pintype "passive"))
      (node (ref "C17") (pin "1") (pinfunction "1_1") (pintype "passive"))
      (node (ref "C2") (pin "1") (pinfunction "1_1") (pintype "passive"))
      (node (ref "C3") (pin "1") (pinfunction "1_1") (pintype "passive"))
      (node (ref "C4") (pin "1") (pinfunction "1_1") (pintype "passive"))
      (node (ref "C5") (pin "1") (pinfunction "1_1") (pintype "passive"))
      (node (ref "C6") (pin "1") (pinfunction "1_1") (pintype "passive"))
      (node (ref "C7") (pin "1") (pinfunction "1_1") (pintype "passive"))
      (node (ref "C8") (pin "1") (pinfunction "1_1") (pintype "passive"))
      (node (ref "C9") (pin "1") (pinfunction "1_1") (pintype "passive"))
      (node (ref "D1") (pin "1") (pinfunction "1_1") (pintype "passive"))
      (node (ref "D2") (pin "1") (pinfunction "1_1") (pintype "passive"))
      (node (ref "D3") (pin "1") (pinfunction "1_1") (pintype "passive"))
      (node (ref "D4") (pin "1") (pinfunction "1_1") (pintype "passive"))
      (node (ref "D6") (pin "1") (pinfunction "1_1") (pintype "passive"))
      (node (ref "D7") (pin "1") (pinfunction "1_1") (pintype "passive"))
      (node (ref "D8") (pin "1") (pinfunction "1_1") (pintype "passive"))
      (node (ref "J1") (pin "1") (pinfunction "1_1") (pintype "passive"))
      (node (ref "J1") (pin "23") (pinfunction "23_23") (pintype "passive"))
      (node (ref "J2") (pin "2") (pinfunction "2_2") (pintype "passive"))
      (node (ref "J2") (pin "24") (pinfunction "24_24") (pintype "passive"))
      (node (ref "J3") (pin "A1B12") (pinfunction "GND_A1B12_A1B12") (pintype "passive"))
      (node (ref "J3") (pin "B1A12") (pinfunction "GND_B1A12_B1A12") (pintype "passive"))
      (node (ref "J3") (pin "S1") (pinfunction "SHIELD_1_S1") (pintype "passive"))
      (node (ref "J3") (pin "S2") (pinfunction "SHIELD_2_S2") (pintype "passive"))
      (node (ref "J3") (pin "S3") (pinfunction "SHIELD_3_S3") (pintype "passive"))
      (node (ref "J3") (pin "S4") (pinfunction "SHIELD_4_S4") (pintype "passive"))
      (node (ref "J4") (pin "A1B12") (pinfunction "GND_A1B12_A1B12") (pintype "passive"))
      (node (ref "J4") (pin "B1A12") (pinfunction "GND_B1A12_B1A12") (pintype "passive"))
      (node (ref "J4") (pin "S1") (pinfunction "SHIELD_1_S1") (pintype "passive"))
      (node (ref "J4") (pin "S2") (pinfunction "SHIELD_2_S2") (pintype "passive"))
      (node (ref "J4") (pin "S3") (pinfunction "SHIELD_3_S3") (pintype "passive"))
      (node (ref "J4") (pin "S4") (pinfunction "SHIELD_4_S4") (pintype "passive"))
      (node (ref "R10") (pin "2") (pinfunction "2_2") (pintype "passive"))
      (node (ref "R11") (pin "1") (pinfunction "1_1") (pintype "passive"))
      (node (ref "R14") (pin "2") (pinfunction "2_2") (pintype "passive"))
      (node (ref "R15") (pin "2") (pinfunction "2_2") (pintype "passive"))
      (node (ref "R7") (pin "2") (pinfunction "2_2") (pintype "passive"))
      (node (ref "R9") (pin "2") (pinfunction "2_2") (pintype "passive"))
      (node (ref "SW1") (pin "3") (pinfunction "3_3") (pintype "passive"))
      (node (ref "SW1") (pin "4") (pinfunction "4_4") (pintype "passive"))
      (node (ref "SW2") (pin "3") (pinfunction "3_3") (pintype "passive"))
      (node (ref "SW2") (pin "4") (pinfunction "4_4") (pintype "passive"))
      (node (ref "U1") (pin "1") (pinfunction "GND_1_1") (pintype "passive"))
      (node (ref "U1") (pin "2") (pinfunction "GND_2_2") (pintype "passive"))
      (node (ref "U1") (pin "42") (pinfunction "GND_42_42") (pintype "passive"))
      (node (ref "U1") (pin "43") (pinfunction "GND_43_43") (pintype "passive"))
      (node (ref "U1") (pin "46") (pinfunction "GND_46_46") (pintype "passive"))
      (node (ref "U1") (pin "47") (pinfunction "GND_47_47") (pintype "passive"))
      (node (ref "U1") (pin "48") (pinfunction "GND_48_48") (pintype "passive"))
      (node (ref "U1") (pin "49") (pinfunction "GND_49_49") (pintype "passive"))
      (node (ref "U1") (pin "50") (pinfunction "GND_50_50") (pintype "passive"))
      (node (ref "U1") (pin "51") (pinfunction "GND_51_51") (pintype "passive"))
      (node (ref "U1") (pin "52") (pinfunction "GND_52_52") (pintype "passive"))
      (node (ref "U1") (pin "53") (pinfunction "GND_53_53") (pintype "passive"))
      (node (ref "U1") (pin "54") (pinfunction "GND_54_54") (pintype "passive"))
      (node (ref "U1") (pin "55") (pinfunction "GND_55_55") (pintype "passive"))
      (node (ref "U1") (pin "56") (pinfunction "GND_56_56") (pintype "passive"))
      (node (ref "U1") (pin "57") (pinfunction "GND_57_57") (pintype "passive"))
      (node (ref "U1") (pin "58") (pinfunction "GND_58_58") (pintype "passive"))
      (node (ref "U1") (pin "59") (pinfunction "GND_59_59") (pintype "passive"))
      (node (ref "U1") (pin "60") (pinfunction "GND_60_60") (pintype "passive"))
      (node (ref "U1") (pin "61") (pinfunction "GND_61_61") (pintype "passive"))
      (node (ref "U1") (pin "62") (pinfunction "GND_62_62") (pintype "passive"))
      (node (ref "U1") (pin "63") (pinfunction "GND_63_63") (pintype "passive"))
      (node (ref "U1") (pin "64") (pinfunction "GND_64_64") (pintype "passive"))
      (node (ref "U1") (pin "65") (pinfunction "GND_65_65") (pintype "passive"))
      (node (ref "U1") (pin "66") (pinfunction "GND_66_66") (pintype "passive"))
      (node (ref "U1") (pin "67") (pinfunction "GND_67_67") (pintype "passive"))
      (node (ref "U1") (pin "68") (pinfunction "GND_68_68") (pintype "passive"))
      (node (ref "U1") (pin "69") (pinfunction "GND_69_69") (pintype "passive"))
      (node (ref "U1") (pin "70") (pinfunction "GND_70_70") (pintype "passive"))
      (node (ref "U1") (pin "71") (pinfunction "GND_71_71") (pintype "passive"))
      (node (ref "U1") (pin "72") (pinfunction "GND_72_72") (pintype "passive"))
      (node (ref "U1") (pin "73") (pinfunction "GND_73_73") (pintype "passive"))
      (node (ref "U2") (pin "13") (pinfunction "GND_13") (pintype "passive"))
      (node (ref "U2") (pin "21") (pinfunction "GND_21") (pintype "passive"))
      (node (ref "U2") (pin "3") (pinfunction "GND_3") (pintype "passive"))
      (node (ref "U3") (pin "2") (pinfunction "GND_2") (pintype "power_in"))
      (node (ref "U3") (pin "4") (pinfunction "GND_4") (pintype "power_in"))
    )
    (net (code "64") (name "Net-(D4-Pad2)") (class "Default")
      (node (ref "D4") (pin "2") (pinfunction "2_2") (pintype "passive"))
      (node (ref "R12") (pin "1") (pinfunction "1_1") (pintype "passive"))
    )
    (net (code "65") (name "Net-(D5-Pad2)") (class "Default")
      (node (ref "D5") (pin "2") (pinfunction "2_2") (pintype "passive"))
      (node (ref "R13") (pin "1") (pinfunction "1_1") (pintype "passive"))
    )
    (net (code "66") (name "Net-(J3-CC1)") (class "Default")
      (node (ref "J3") (pin "A5") (pinfunction "CC1_A5") (pintype "passive"))
      (node (ref "R10") (pin "1") (pinfunction "1_1") (pintype "passive"))
    )
    (net (code "67") (name "Net-(J3-CC2)") (class "Default")
      (node (ref "J3") (pin "B5") (pinfunction "CC2_B5") (pintype "passive"))
      (node (ref "R9") (pin "1") (pinfunction "1_1") (pintype "passive"))
    )
    (net (code "68") (name "Net-(J4-CC1)") (class "Default")
      (node (ref "J4") (pin "A5") (pinfunction "CC1_A5") (pintype "passive"))
      (node (ref "R15") (pin "1") (pinfunction "1_1") (pintype "passive"))
    )
    (net (code "69") (name "Net-(J4-CC2)") (class "Default")
      (node (ref "J4") (pin "B5") (pinfunction "CC2_B5") (pintype "passive"))
      (node (ref "R14") (pin "1") (pinfunction "1_1") (pintype "passive"))
    )
    (net (code "70") (name "Net-(Q1-B)") (class "Default")
      (node (ref "Q1") (pin "1") (pinfunction "B_1") (pintype "passive"))
      (node (ref "R16") (pin "2") (pinfunction "2_2") (pintype "passive"))
    )
    (net (code "71") (name "Net-(Q2-B)") (class "Default")
      (node (ref "Q2") (pin "1") (pinfunction "B_1") (pintype "passive"))
      (node (ref "R17") (pin "2") (pinfunction "2_2") (pintype "passive"))
    )
    (net (code "72") (name "Net-(U2-CBUS0)") (class "Default")
      (node (ref "R7") (pin "1") (pinfunction "1_1") (pintype "passive"))
      (node (ref "U2") (pin "15") (pinfunction "CBUS0_15") (pintype "passive"))
    )
    (net (code "73") (name "Net-(U2-VCC)") (class "Default")
      (node (ref "C4") (pin "2") (pinfunction "2_2") (pintype "passive"))
      (node (ref "C5") (pin "2") (pinfunction "2_2") (pintype "passive"))
      (node (ref "R1") (pin "2") (pinfunction "2_2") (pintype "passive"))
      (node (ref "R2") (pin "2") (pinfunction "2_2") (pintype "passive"))
      (node (ref "U2") (pin "12") (pinfunction "VCC_12") (pintype "passive"))
    )
    (net (code "74") (name "unconnected-(J1-Pad24)") (class "Default")
      (node (ref "J1") (pin "24") (pinfunction "24_24") (pintype "passive+no_connect"))
    )
    (net (code "75") (name "unconnected-(J3-SBU1-PadA8)") (class "Default")
      (node (ref "J3") (pin "A8") (pinfunction "SBU1_A8") (pintype "passive+no_connect"))
    )
    (net (code "76") (name "unconnected-(J3-SBU2-PadB8)") (class "Default")
      (node (ref "J3") (pin "B8") (pinfunction "SBU2_B8") (pintype "passive+no_connect"))
    )
    (net (code "77") (name "unconnected-(J4-SBU1-PadA8)") (class "Default")
      (node (ref "J4") (pin "A8") (pinfunction "SBU1_A8") (pintype "passive+no_connect"))
    )
    (net (code "78") (name "unconnected-(J4-SBU2-PadB8)") (class "Default")
      (node (ref "J4") (pin "B8") (pinfunction "SBU2_B8") (pintype "passive+no_connect"))
    )
    (net (code "79") (name "unconnected-(U2-CBUS1-Pad14)") (class "Default")
      (node (ref "U2") (pin "14") (pinfunction "CBUS1_14") (pintype "passive+no_connect"))
    )
    (net (code "80") (name "unconnected-(U2-CBUS2-Pad7)") (class "Default")
      (node (ref "U2") (pin "7") (pinfunction "CBUS2_7") (pintype "passive+no_connect"))
    )
    (net (code "81") (name "unconnected-(U2-~{CTS}-Pad6)") (class "Default")
      (node (ref "U2") (pin "6") (pinfunction "~{CTS}_6") (pintype "input+no_connect"))
    )
    (net (code "82") (name "unconnected-(U2-~{DCD}-Pad5)") (class "Default")
      (node (ref "U2") (pin "5") (pinfunction "~{DCD}_5") (pintype "input+no_connect"))
    )
    (net (code "83") (name "unconnected-(U2-~{DSR}-Pad4)") (class "Default")
      (node (ref "U2") (pin "4") (pinfunction "~{DSR}_4") (pintype "input+no_connect"))
    )
    (net (code "84") (name "unconnected-(U2-~{RI}-Pad2)") (class "Default")
      (node (ref "U2") (pin "2") (pinfunction "~{RI}_2") (pintype "input+no_connect"))
    )
  )
)
